# 19_SOLEDNOID.net
KiCad netlist of a schematic drawn in Altium Designer
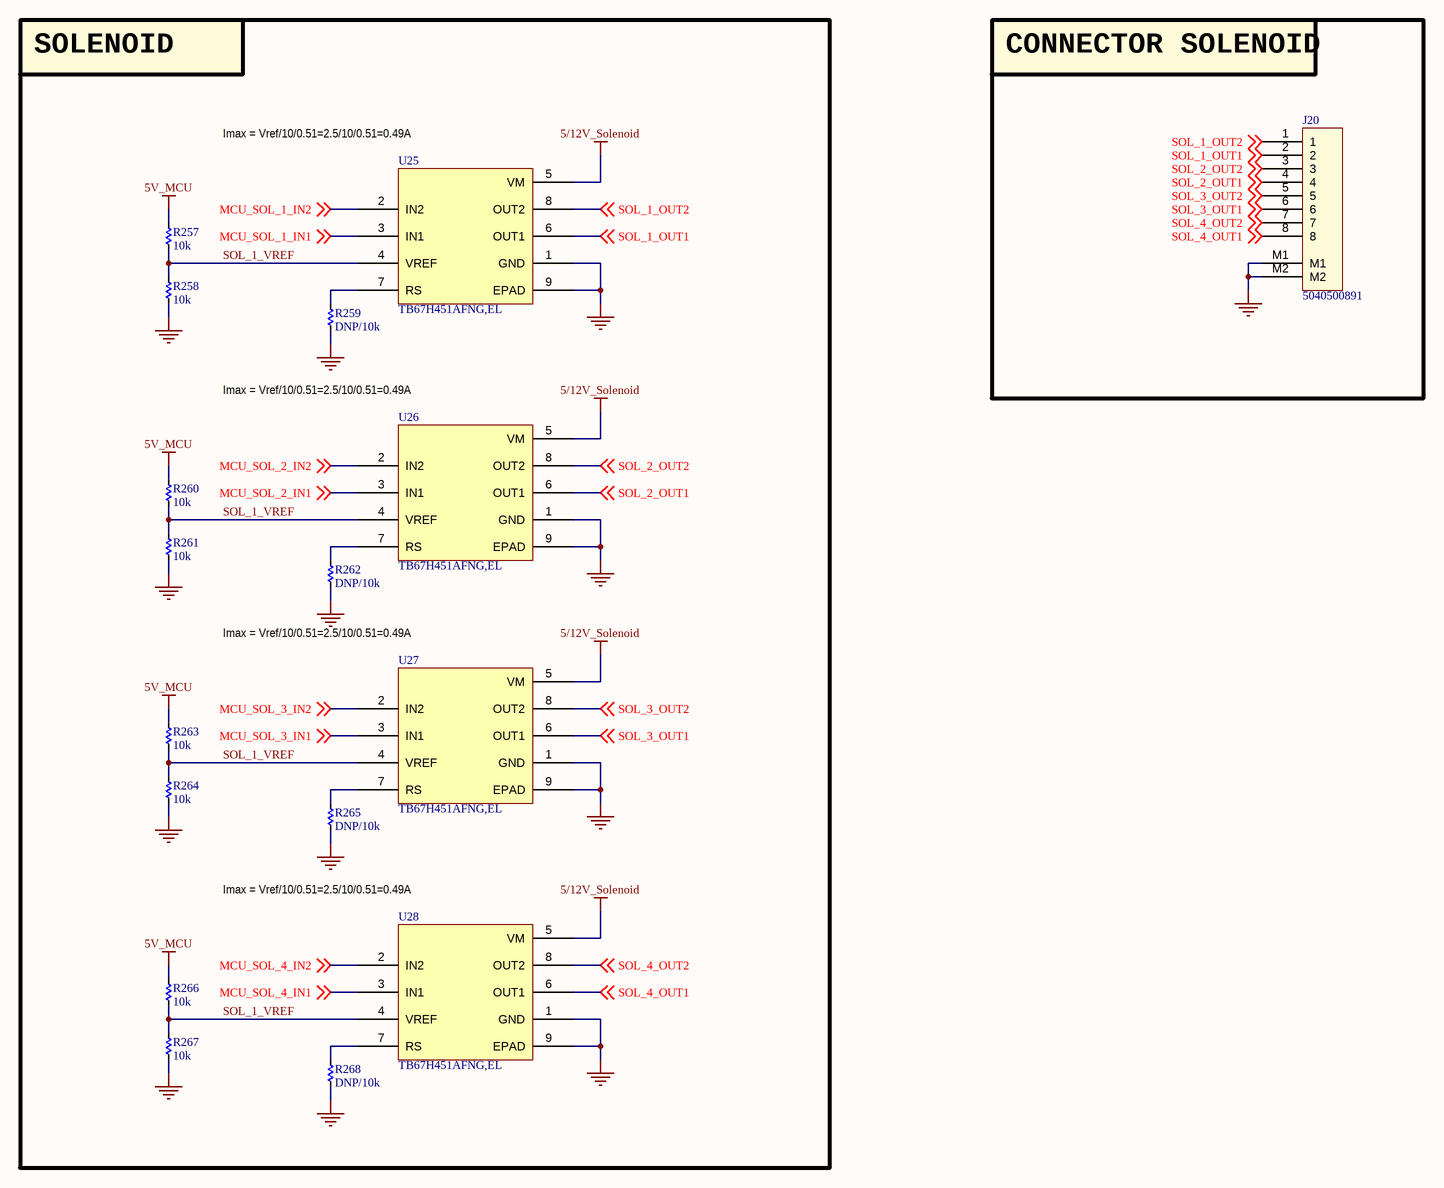
[diagram p0: 19_SOLEDNOID.SchDoc]

(export (version "E")
  (design (tool "Eeschema 10.0.6"))
  (components
    (comp (ref "J20")
      (value "5040500891")
      (footprint "MOLEX_5040500891")
      (libsource (lib "LABLIB") (part "Header 8x1_2M"))
    )
    (comp (ref "R257")
      (value "10k")
      (footprint "RES_C_1005X40")
      (description "RES")
      (libsource (lib "LABLIB") (part "_RES_B_2"))
    )
    (comp (ref "R258")
      (value "10k")
      (footprint "RES_C_1005X40")
      (description "RES")
      (libsource (lib "LABLIB") (part "_RES_B_2"))
    )
    (comp (ref "R259")
      (value "DNP/10k")
      (footprint "RES_C_1005X40")
      (description "RES")
      (libsource (lib "LABLIB") (part "_RES_B_2"))
    )
    (comp (ref "R260")
      (value "10k")
      (footprint "RES_C_1005X40")
      (description "RES")
      (libsource (lib "LABLIB") (part "_RES_B_2"))
    )
    (comp (ref "R261")
      (value "10k")
      (footprint "RES_C_1005X40")
      (description "RES")
      (libsource (lib "LABLIB") (part "_RES_B_2"))
    )
    (comp (ref "R262")
      (value "DNP/10k")
      (footprint "RES_C_1005X40")
      (description "RES")
      (libsource (lib "LABLIB") (part "_RES_B_2"))
    )
    (comp (ref "R263")
      (value "10k")
      (footprint "RES_C_1005X40")
      (description "RES")
      (libsource (lib "LABLIB") (part "_RES_B_2"))
    )
    (comp (ref "R264")
      (value "10k")
      (footprint "RES_C_1005X40")
      (description "RES")
      (libsource (lib "LABLIB") (part "_RES_B_2"))
    )
    (comp (ref "R265")
      (value "DNP/10k")
      (footprint "RES_C_1005X40")
      (description "RES")
      (libsource (lib "LABLIB") (part "_RES_B_2"))
    )
    (comp (ref "R266")
      (value "10k")
      (footprint "RES_C_1005X40")
      (description "RES")
      (libsource (lib "LABLIB") (part "_RES_B_2"))
    )
    (comp (ref "R267")
      (value "10k")
      (footprint "RES_C_1005X40")
      (description "RES")
      (libsource (lib "LABLIB") (part "_RES_B_2"))
    )
    (comp (ref "R268")
      (value "DNP/10k")
      (footprint "RES_C_1005X40")
      (description "RES")
      (libsource (lib "LABLIB") (part "_RES_B_2"))
    )
    (comp (ref "U25")
      (value "TB67H451AFNG,EL")
      (description "BRUSHED MOTOR DRIVER IC, 50V, 3.")
      (libsource (lib "LABLIB") (part "IC_H_bridge_TB67H451AFNG,EL"))
    )
    (comp (ref "U26")
      (value "TB67H451AFNG,EL")
      (description "BRUSHED MOTOR DRIVER IC, 50V, 3.")
      (libsource (lib "LABLIB") (part "IC_H_bridge_TB67H451AFNG,EL"))
    )
    (comp (ref "U27")
      (value "TB67H451AFNG,EL")
      (description "BRUSHED MOTOR DRIVER IC, 50V, 3.")
      (libsource (lib "LABLIB") (part "IC_H_bridge_TB67H451AFNG,EL"))
    )
    (comp (ref "U28")
      (value "TB67H451AFNG,EL")
      (description "BRUSHED MOTOR DRIVER IC, 50V, 3.")
      (libsource (lib "LABLIB") (part "IC_H_bridge_TB67H451AFNG,EL"))
    )
  )
  (nets
    (net (code "1") (name "/SOL_1_VREF") (class "Default")
      (node (ref "R257") (pin "2") (pinfunction "2_2") (pintype "passive"))
      (node (ref "R258") (pin "1") (pinfunction "1_1") (pintype "passive"))
      (node (ref "R260") (pin "2") (pinfunction "2_2") (pintype "passive"))
      (node (ref "R261") (pin "1") (pinfunction "1_1") (pintype "passive"))
      (node (ref "R263") (pin "2") (pinfunction "2_2") (pintype "passive"))
      (node (ref "R264") (pin "1") (pinfunction "1_1") (pintype "passive"))
      (node (ref "R266") (pin "2") (pinfunction "2_2") (pintype "passive"))
      (node (ref "R267") (pin "1") (pinfunction "1_1") (pintype "passive"))
      (node (ref "U25") (pin "4") (pinfunction "VREF_4") (pintype "passive"))
      (node (ref "U26") (pin "4") (pinfunction "VREF_4") (pintype "passive"))
      (node (ref "U27") (pin "4") (pinfunction "VREF_4") (pintype "passive"))
      (node (ref "U28") (pin "4") (pinfunction "VREF_4") (pintype "passive"))
    )
    (net (code "2") (name "5V_MCU") (class "Default")
      (node (ref "R257") (pin "1") (pinfunction "1_1") (pintype "passive"))
      (node (ref "R260") (pin "1") (pinfunction "1_1") (pintype "passive"))
      (node (ref "R263") (pin "1") (pinfunction "1_1") (pintype "passive"))
      (node (ref "R266") (pin "1") (pinfunction "1_1") (pintype "passive"))
    )
    (net (code "3") (name "5{slash}12V_Solenoid") (class "Default")
      (node (ref "U25") (pin "5") (pinfunction "VM_5") (pintype "passive"))
      (node (ref "U26") (pin "5") (pinfunction "VM_5") (pintype "passive"))
      (node (ref "U27") (pin "5") (pinfunction "VM_5") (pintype "passive"))
      (node (ref "U28") (pin "5") (pinfunction "VM_5") (pintype "passive"))
    )
    (net (code "4") (name "GND") (class "Default")
      (node (ref "J20") (pin "M1") (pinfunction "M1_M1") (pintype "passive"))
      (node (ref "J20") (pin "M2") (pinfunction "M2_M2") (pintype "passive"))
      (node (ref "R258") (pin "2") (pinfunction "2_2") (pintype "passive"))
      (node (ref "R259") (pin "2") (pinfunction "2_2") (pintype "passive"))
      (node (ref "R261") (pin "2") (pinfunction "2_2") (pintype "passive"))
      (node (ref "R262") (pin "2") (pinfunction "2_2") (pintype "passive"))
      (node (ref "R264") (pin "2") (pinfunction "2_2") (pintype "passive"))
      (node (ref "R265") (pin "2") (pinfunction "2_2") (pintype "passive"))
      (node (ref "R267") (pin "2") (pinfunction "2_2") (pintype "passive"))
      (node (ref "R268") (pin "2") (pinfunction "2_2") (pintype "passive"))
      (node (ref "U25") (pin "1") (pinfunction "GND_1") (pintype "passive"))
      (node (ref "U25") (pin "9") (pinfunction "EPAD_9") (pintype "passive"))
      (node (ref "U26") (pin "1") (pinfunction "GND_1") (pintype "passive"))
      (node (ref "U26") (pin "9") (pinfunction "EPAD_9") (pintype "passive"))
      (node (ref "U27") (pin "1") (pinfunction "GND_1") (pintype "passive"))
      (node (ref "U27") (pin "9") (pinfunction "EPAD_9") (pintype "passive"))
      (node (ref "U28") (pin "1") (pinfunction "GND_1") (pintype "passive"))
      (node (ref "U28") (pin "9") (pinfunction "EPAD_9") (pintype "passive"))
    )
    (net (code "5") (name "MCU_SOL_1_IN1") (class "Default")
      (node (ref "U25") (pin "3") (pinfunction "IN1_3") (pintype "passive"))
    )
    (net (code "6") (name "MCU_SOL_1_IN2") (class "Default")
      (node (ref "U25") (pin "2") (pinfunction "IN2_2") (pintype "passive"))
    )
    (net (code "7") (name "MCU_SOL_2_IN1") (class "Default")
      (node (ref "U26") (pin "3") (pinfunction "IN1_3") (pintype "passive"))
    )
    (net (code "8") (name "MCU_SOL_2_IN2") (class "Default")
      (node (ref "U26") (pin "2") (pinfunction "IN2_2") (pintype "passive"))
    )
    (net (code "9") (name "MCU_SOL_3_IN1") (class "Default")
      (node (ref "U27") (pin "3") (pinfunction "IN1_3") (pintype "passive"))
    )
    (net (code "10") (name "MCU_SOL_3_IN2") (class "Default")
      (node (ref "U27") (pin "2") (pinfunction "IN2_2") (pintype "passive"))
    )
    (net (code "11") (name "MCU_SOL_4_IN1") (class "Default")
      (node (ref "U28") (pin "3") (pinfunction "IN1_3") (pintype "passive"))
    )
    (net (code "12") (name "MCU_SOL_4_IN2") (class "Default")
      (node (ref "U28") (pin "2") (pinfunction "IN2_2") (pintype "passive"))
    )
    (net (code "13") (name "Net-(U25-RS)") (class "Default")
      (node (ref "R259") (pin "1") (pinfunction "1_1") (pintype "passive"))
      (node (ref "U25") (pin "7") (pinfunction "RS_7") (pintype "passive"))
    )
    (net (code "14") (name "Net-(U26-RS)") (class "Default")
      (node (ref "R262") (pin "1") (pinfunction "1_1") (pintype "passive"))
      (node (ref "U26") (pin "7") (pinfunction "RS_7") (pintype "passive"))
    )
    (net (code "15") (name "Net-(U27-RS)") (class "Default")
      (node (ref "R265") (pin "1") (pinfunction "1_1") (pintype "passive"))
      (node (ref "U27") (pin "7") (pinfunction "RS_7") (pintype "passive"))
    )
    (net (code "16") (name "Net-(U28-RS)") (class "Default")
      (node (ref "R268") (pin "1") (pinfunction "1_1") (pintype "passive"))
      (node (ref "U28") (pin "7") (pinfunction "RS_7") (pintype "passive"))
    )
    (net (code "17") (name "SOL_1_OUT1") (class "Default")
      (node (ref "J20") (pin "2") (pinfunction "2_2") (pintype "passive"))
      (node (ref "U25") (pin "6") (pinfunction "OUT1_6") (pintype "passive"))
    )
    (net (code "18") (name "SOL_1_OUT2") (class "Default")
      (node (ref "J20") (pin "1") (pinfunction "1_1") (pintype "passive"))
      (node (ref "U25") (pin "8") (pinfunction "OUT2_8") (pintype "passive"))
    )
    (net (code "19") (name "SOL_2_OUT1") (class "Default")
      (node (ref "J20") (pin "4") (pinfunction "4_4") (pintype "passive"))
      (node (ref "U26") (pin "6") (pinfunction "OUT1_6") (pintype "passive"))
    )
    (net (code "20") (name "SOL_2_OUT2") (class "Default")
      (node (ref "J20") (pin "3") (pinfunction "3_3") (pintype "passive"))
      (node (ref "U26") (pin "8") (pinfunction "OUT2_8") (pintype "passive"))
    )
    (net (code "21") (name "SOL_3_OUT1") (class "Default")
      (node (ref "J20") (pin "6") (pinfunction "6_6") (pintype "passive"))
      (node (ref "U27") (pin "6") (pinfunction "OUT1_6") (pintype "passive"))
    )
    (net (code "22") (name "SOL_3_OUT2") (class "Default")
      (node (ref "J20") (pin "5") (pinfunction "5_5") (pintype "passive"))
      (node (ref "U27") (pin "8") (pinfunction "OUT2_8") (pintype "passive"))
    )
    (net (code "23") (name "SOL_4_OUT1") (class "Default")
      (node (ref "J20") (pin "8") (pinfunction "8_8") (pintype "passive"))
      (node (ref "U28") (pin "6") (pinfunction "OUT1_6") (pintype "passive"))
    )
    (net (code "24") (name "SOL_4_OUT2") (class "Default")
      (node (ref "J20") (pin "7") (pinfunction "7_7") (pintype "passive"))
      (node (ref "U28") (pin "8") (pinfunction "OUT2_8") (pintype "passive"))
    )
  )
)
